# ARE_adaptadora_PIC_44pin.net
KiCad netlist of a schematic drawn in EAGLE
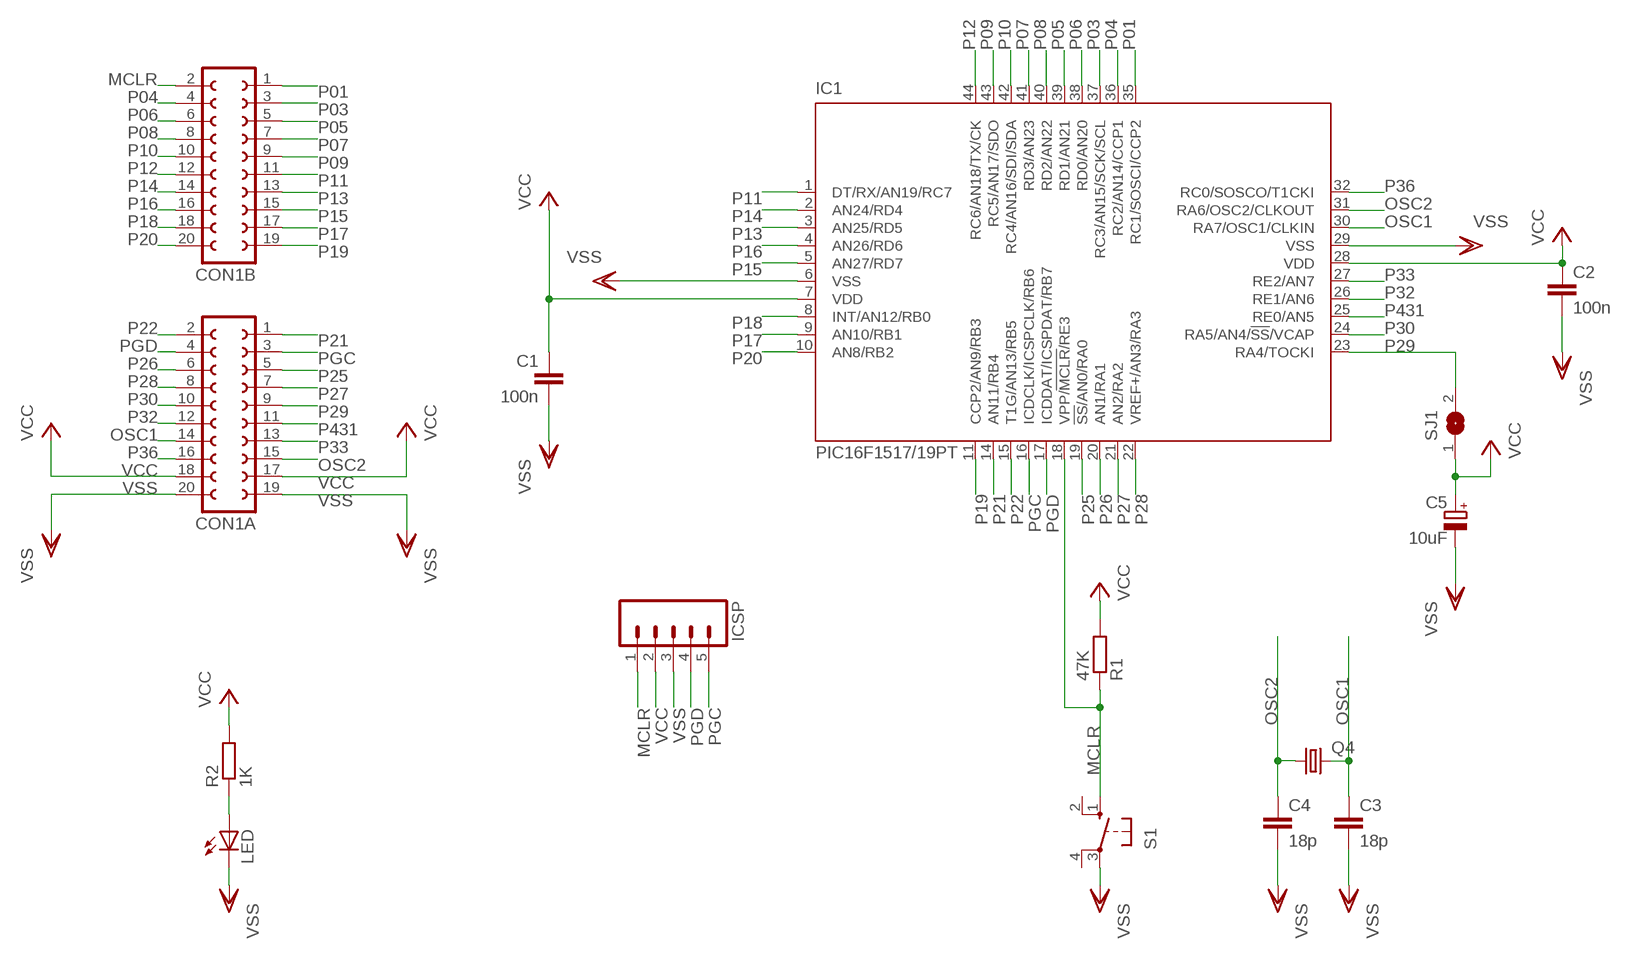
[diagram p0: schematic, sheet 1]

(export (version "E")
  (design (tool "Eeschema 10.0.6"))
  (components
    (comp (ref "C1")
      (value "100n")
      (footprint "eagle-import:C0805")
      (libsource (lib "eagle-import") (part "C-EUC0805"))
    )
    (comp (ref "C2")
      (value "100n")
      (footprint "eagle-import:C0805")
      (libsource (lib "eagle-import") (part "C-EUC0805"))
    )
    (comp (ref "C3")
      (value "18p")
      (footprint "eagle-import:C0805")
      (libsource (lib "eagle-import") (part "C-EUC0805"))
    )
    (comp (ref "C4")
      (value "18p")
      (footprint "eagle-import:C0805")
      (libsource (lib "eagle-import") (part "C-EUC0805"))
    )
    (comp (ref "C5")
      (value "10uF")
      (footprint "eagle-import:SMC_C")
      (libsource (lib "eagle-import") (part "CPOL-EUSMCC"))
    )
    (comp (ref "CON1A")
      (value "FE10-2W")
      (footprint "eagle-import:FE10-2W")
      (libsource (lib "eagle-import") (part "FE10-2W"))
    )
    (comp (ref "CON1B")
      (value "FE10-2W")
      (footprint "eagle-import:FE10-2W")
      (libsource (lib "eagle-import") (part "FE10-2W"))
    )
    (comp (ref "IC1")
      (value "PIC16F1517/19PT")
      (footprint "eagle-import:TQFP44")
      (libsource (lib "eagle-import") (part "PIC16F1517/19PT"))
    )
    (comp (ref "ICSP")
      (value "M05PTH")
      (footprint "eagle-import:1X05")
      (libsource (lib "eagle-import") (part "M05PTH"))
    )
    (comp (ref "LED")
      (value "LEDCHIPLED_0805")
      (footprint "eagle-import:CHIPLED_0805")
      (libsource (lib "eagle-import") (part "LEDCHIPLED_0805"))
    )
    (comp (ref "Q4")
      (value "CRYSTALHC18U-V")
      (footprint "eagle-import:HC18U-V")
      (libsource (lib "eagle-import") (part "CRYSTALHC18U-V"))
    )
    (comp (ref "R1")
      (value "47K")
      (footprint "eagle-import:R0805")
      (libsource (lib "eagle-import") (part "R-EU_R0805"))
    )
    (comp (ref "R2")
      (value "1K")
      (footprint "eagle-import:R0805")
      (libsource (lib "eagle-import") (part "R-EU_R0805"))
    )
    (comp (ref "S1")
      (value "10-XX")
      (footprint "eagle-import:B3F-10XX")
      (fields
        (field (name "MPN") "B3F-1000")
        (field (name "MPN_1") "B3F-1000")
        (field (name "OC_FARNELL") "176432")
        (field (name "OC_NEWARK") "36M3542")
      )
      (libsource (lib "eagle-import") (part "10-XX"))
    )
    (comp (ref "SJ1") (value "SJ") (footprint "eagle-import:SJ") (libsource (lib "eagle-import") (part "SJ")))
  )
  (nets
    (net (code "1") (name "/MCLR") (class "Default")
      (node (ref "CON1B") (pin "2") (pinfunction "2_2") (pintype "passive"))
      (node (ref "IC1") (pin "18") (pinfunction "VPP/~{MCLR}/RE3_18") (pintype "input"))
      (node (ref "ICSP") (pin "1") (pinfunction "1_1") (pintype "passive"))
      (node (ref "R1") (pin "1") (pinfunction "1_1") (pintype "passive"))
      (node (ref "S1") (pin "1") (pinfunction "S_1") (pintype "passive"))
    )
    (net (code "2") (name "/OSC1") (class "Default")
      (node (ref "C3") (pin "1") (pinfunction "1_1") (pintype "passive"))
      (node (ref "CON1A") (pin "14") (pinfunction "14_14") (pintype "passive"))
      (node (ref "IC1") (pin "30") (pinfunction "RA7/OSC1/CLKIN_30") (pintype "bidirectional"))
      (node (ref "Q4") (pin "2") (pinfunction "2_2") (pintype "passive"))
    )
    (net (code "3") (name "/OSC2") (class "Default")
      (node (ref "C4") (pin "1") (pinfunction "1_1") (pintype "passive"))
      (node (ref "CON1A") (pin "15") (pinfunction "15_15") (pintype "passive"))
      (node (ref "IC1") (pin "31") (pinfunction "RA6/OSC2/CLKOUT_31") (pintype "bidirectional"))
      (node (ref "Q4") (pin "1") (pinfunction "1_1") (pintype "passive"))
    )
    (net (code "4") (name "/P01") (class "Default")
      (node (ref "CON1B") (pin "1") (pinfunction "1_1") (pintype "passive"))
      (node (ref "IC1") (pin "35") (pinfunction "RC1/SOSCI/CCP2_35") (pintype "bidirectional"))
    )
    (net (code "5") (name "/P03") (class "Default")
      (node (ref "CON1B") (pin "3") (pinfunction "3_3") (pintype "passive"))
      (node (ref "IC1") (pin "37") (pinfunction "RC3/AN15/SCK/SCL_37") (pintype "bidirectional"))
    )
    (net (code "6") (name "/P04") (class "Default")
      (node (ref "CON1B") (pin "4") (pinfunction "4_4") (pintype "passive"))
      (node (ref "IC1") (pin "36") (pinfunction "RC2/AN14/CCP1_36") (pintype "bidirectional"))
    )
    (net (code "7") (name "/P05") (class "Default")
      (node (ref "CON1B") (pin "5") (pinfunction "5_5") (pintype "passive"))
      (node (ref "IC1") (pin "39") (pinfunction "RD1/AN21_39") (pintype "bidirectional"))
    )
    (net (code "8") (name "/P06") (class "Default")
      (node (ref "CON1B") (pin "6") (pinfunction "6_6") (pintype "passive"))
      (node (ref "IC1") (pin "38") (pinfunction "RD0/AN20_38") (pintype "bidirectional"))
    )
    (net (code "9") (name "/P07") (class "Default")
      (node (ref "CON1B") (pin "7") (pinfunction "7_7") (pintype "passive"))
      (node (ref "IC1") (pin "41") (pinfunction "RD3/AN23_41") (pintype "bidirectional"))
    )
    (net (code "10") (name "/P08") (class "Default")
      (node (ref "CON1B") (pin "8") (pinfunction "8_8") (pintype "passive"))
      (node (ref "IC1") (pin "40") (pinfunction "RD2/AN22_40") (pintype "bidirectional"))
    )
    (net (code "11") (name "/P09") (class "Default")
      (node (ref "CON1B") (pin "9") (pinfunction "9_9") (pintype "passive"))
      (node (ref "IC1") (pin "43") (pinfunction "RC5/AN17/SDO_43") (pintype "bidirectional"))
    )
    (net (code "12") (name "/P10") (class "Default")
      (node (ref "CON1B") (pin "10") (pinfunction "10_10") (pintype "passive"))
      (node (ref "IC1") (pin "42") (pinfunction "RC4/AN16/SDI/SDA_42") (pintype "bidirectional"))
    )
    (net (code "13") (name "/P11") (class "Default")
      (node (ref "CON1B") (pin "11") (pinfunction "11_11") (pintype "passive"))
      (node (ref "IC1") (pin "1") (pinfunction "DT/RX/AN19/RC7_1") (pintype "bidirectional"))
    )
    (net (code "14") (name "/P12") (class "Default")
      (node (ref "CON1B") (pin "12") (pinfunction "12_12") (pintype "passive"))
      (node (ref "IC1") (pin "44") (pinfunction "RC6/AN18/TX/CK_44") (pintype "bidirectional"))
    )
    (net (code "15") (name "/P13") (class "Default")
      (node (ref "CON1B") (pin "13") (pinfunction "13_13") (pintype "passive"))
      (node (ref "IC1") (pin "3") (pinfunction "AN25/RD5_3") (pintype "bidirectional"))
    )
    (net (code "16") (name "/P14") (class "Default")
      (node (ref "CON1B") (pin "14") (pinfunction "14_14") (pintype "passive"))
      (node (ref "IC1") (pin "2") (pinfunction "AN24/RD4_2") (pintype "bidirectional"))
    )
    (net (code "17") (name "/P15") (class "Default")
      (node (ref "CON1B") (pin "15") (pinfunction "15_15") (pintype "passive"))
      (node (ref "IC1") (pin "5") (pinfunction "AN27/RD7_5") (pintype "bidirectional"))
    )
    (net (code "18") (name "/P16") (class "Default")
      (node (ref "CON1B") (pin "16") (pinfunction "16_16") (pintype "passive"))
      (node (ref "IC1") (pin "4") (pinfunction "AN26/RD6_4") (pintype "bidirectional"))
    )
    (net (code "19") (name "/P17") (class "Default")
      (node (ref "CON1B") (pin "17") (pinfunction "17_17") (pintype "passive"))
      (node (ref "IC1") (pin "9") (pinfunction "AN10/RB1_9") (pintype "bidirectional"))
    )
    (net (code "20") (name "/P18") (class "Default")
      (node (ref "CON1B") (pin "18") (pinfunction "18_18") (pintype "passive"))
      (node (ref "IC1") (pin "8") (pinfunction "INT/AN12/RB0_8") (pintype "bidirectional"))
    )
    (net (code "21") (name "/P19") (class "Default")
      (node (ref "CON1B") (pin "19") (pinfunction "19_19") (pintype "passive"))
      (node (ref "IC1") (pin "11") (pinfunction "CCP2/AN9/RB3_11") (pintype "bidirectional"))
    )
    (net (code "22") (name "/P20") (class "Default")
      (node (ref "CON1B") (pin "20") (pinfunction "20_20") (pintype "passive"))
      (node (ref "IC1") (pin "10") (pinfunction "AN8/RB2_10") (pintype "bidirectional"))
    )
    (net (code "23") (name "/P21") (class "Default")
      (node (ref "CON1A") (pin "1") (pinfunction "1_1") (pintype "passive"))
      (node (ref "IC1") (pin "14") (pinfunction "AN11/RB4_14") (pintype "bidirectional"))
    )
    (net (code "24") (name "/P22") (class "Default")
      (node (ref "CON1A") (pin "2") (pinfunction "2_2") (pintype "passive"))
      (node (ref "IC1") (pin "15") (pinfunction "T1G/AN13/RB5_15") (pintype "bidirectional"))
    )
    (net (code "25") (name "/P25") (class "Default")
      (node (ref "CON1A") (pin "5") (pinfunction "5_5") (pintype "passive"))
      (node (ref "IC1") (pin "19") (pinfunction "~{SS}/AN0/RA0_19") (pintype "bidirectional"))
    )
    (net (code "26") (name "/P26") (class "Default")
      (node (ref "CON1A") (pin "6") (pinfunction "6_6") (pintype "passive"))
      (node (ref "IC1") (pin "20") (pinfunction "AN1/RA1_20") (pintype "bidirectional"))
    )
    (net (code "27") (name "/P27") (class "Default")
      (node (ref "CON1A") (pin "7") (pinfunction "7_7") (pintype "passive"))
      (node (ref "IC1") (pin "21") (pinfunction "AN2/RA2_21") (pintype "bidirectional"))
    )
    (net (code "28") (name "/P28") (class "Default")
      (node (ref "CON1A") (pin "8") (pinfunction "8_8") (pintype "passive"))
      (node (ref "IC1") (pin "22") (pinfunction "VREF+/AN3/RA3_22") (pintype "bidirectional"))
    )
    (net (code "29") (name "/P29") (class "Default")
      (node (ref "CON1A") (pin "9") (pinfunction "9_9") (pintype "passive"))
      (node (ref "IC1") (pin "23") (pinfunction "RA4/TOCKI_23") (pintype "bidirectional"))
      (node (ref "SJ1") (pin "2") (pinfunction "2_2") (pintype "passive"))
    )
    (net (code "30") (name "/P30") (class "Default")
      (node (ref "CON1A") (pin "10") (pinfunction "10_10") (pintype "passive"))
      (node (ref "IC1") (pin "24") (pinfunction "RA5/AN4/~{SS}/VCAP_24") (pintype "bidirectional"))
    )
    (net (code "31") (name "/P32") (class "Default")
      (node (ref "CON1A") (pin "12") (pinfunction "12_12") (pintype "passive"))
      (node (ref "IC1") (pin "26") (pinfunction "RE1/AN6_26") (pintype "bidirectional"))
    )
    (net (code "32") (name "/P33") (class "Default")
      (node (ref "CON1A") (pin "13") (pinfunction "13_13") (pintype "passive"))
      (node (ref "IC1") (pin "27") (pinfunction "RE2/AN7_27") (pintype "bidirectional"))
    )
    (net (code "33") (name "/P36") (class "Default")
      (node (ref "CON1A") (pin "16") (pinfunction "16_16") (pintype "passive"))
      (node (ref "IC1") (pin "32") (pinfunction "RC0/SOSCO/T1CKI_32") (pintype "bidirectional"))
    )
    (net (code "34") (name "/P431") (class "Default")
      (node (ref "CON1A") (pin "11") (pinfunction "11_11") (pintype "passive"))
      (node (ref "IC1") (pin "25") (pinfunction "RE0/AN5_25") (pintype "bidirectional"))
    )
    (net (code "35") (name "/PGC") (class "Default")
      (node (ref "CON1A") (pin "3") (pinfunction "3_3") (pintype "passive"))
      (node (ref "IC1") (pin "16") (pinfunction "ICDCLK/ICSPCLK/RB6_16") (pintype "bidirectional"))
      (node (ref "ICSP") (pin "5") (pinfunction "5_5") (pintype "passive"))
    )
    (net (code "36") (name "/PGD") (class "Default")
      (node (ref "CON1A") (pin "4") (pinfunction "4_4") (pintype "passive"))
      (node (ref "IC1") (pin "17") (pinfunction "ICDDAT/ICSPDAT/RB7_17") (pintype "bidirectional"))
      (node (ref "ICSP") (pin "4") (pinfunction "4_4") (pintype "passive"))
    )
    (net (code "37") (name "Net-(LED-PadA)") (class "Default")
      (node (ref "LED") (pin "A") (pinfunction "A_A") (pintype "passive"))
      (node (ref "R2") (pin "1") (pinfunction "1_1") (pintype "passive"))
    )
    (net (code "38") (name "VCC") (class "Default")
      (node (ref "C1") (pin "1") (pinfunction "1_1") (pintype "passive"))
      (node (ref "C2") (pin "1") (pinfunction "1_1") (pintype "passive"))
      (node (ref "C5") (pin "+") (pinfunction "+_+") (pintype "passive"))
      (node (ref "CON1A") (pin "17") (pinfunction "17_17") (pintype "passive"))
      (node (ref "CON1A") (pin "18") (pinfunction "18_18") (pintype "passive"))
      (node (ref "IC1") (pin "28") (pinfunction "VDD_28") (pintype "power_in"))
      (node (ref "IC1") (pin "7") (pinfunction "VDD_7") (pintype "power_in"))
      (node (ref "ICSP") (pin "2") (pinfunction "2_2") (pintype "passive"))
      (node (ref "R1") (pin "2") (pinfunction "2_2") (pintype "passive"))
      (node (ref "R2") (pin "2") (pinfunction "2_2") (pintype "passive"))
      (node (ref "SJ1") (pin "1") (pinfunction "1_1") (pintype "passive"))
    )
    (net (code "39") (name "VSS") (class "Default")
      (node (ref "C1") (pin "2") (pinfunction "2_2") (pintype "passive"))
      (node (ref "C2") (pin "2") (pinfunction "2_2") (pintype "passive"))
      (node (ref "C3") (pin "2") (pinfunction "2_2") (pintype "passive"))
      (node (ref "C4") (pin "2") (pinfunction "2_2") (pintype "passive"))
      (node (ref "C5") (pin "-") (pinfunction "-_-") (pintype "passive"))
      (node (ref "CON1A") (pin "19") (pinfunction "19_19") (pintype "passive"))
      (node (ref "CON1A") (pin "20") (pinfunction "20_20") (pintype "passive"))
      (node (ref "IC1") (pin "29") (pinfunction "VSS_29") (pintype "power_in"))
      (node (ref "IC1") (pin "6") (pinfunction "VSS_6") (pintype "power_in"))
      (node (ref "ICSP") (pin "3") (pinfunction "3_3") (pintype "passive"))
      (node (ref "LED") (pin "C") (pinfunction "C_C") (pintype "passive"))
      (node (ref "S1") (pin "3") (pinfunction "P_3") (pintype "passive"))
    )
    (net (code "40") (name "unconnected-(S1-P1-Pad4)") (class "Default")
      (node (ref "S1") (pin "4") (pinfunction "P1_4") (pintype "passive"))
    )
    (net (code "41") (name "unconnected-(S1-S1-Pad2)") (class "Default")
      (node (ref "S1") (pin "2") (pinfunction "S1_2") (pintype "passive"))
    )
  )
)
